# Sim.net
KiCad netlist of a schematic drawn in Altium Designer
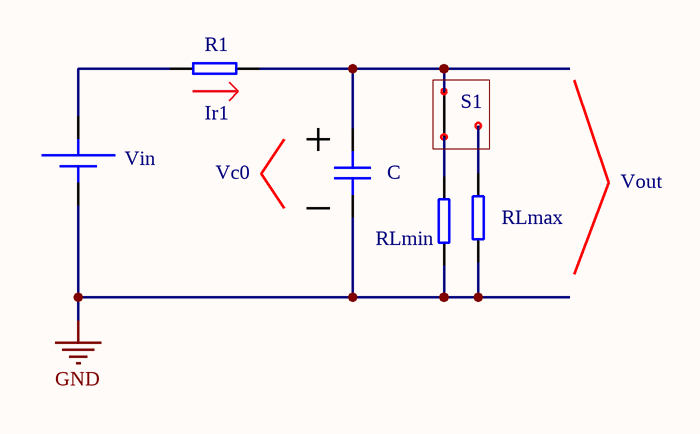
[diagram p0: Sim.SchDoc]

(export (version "E")
  (design (tool "Eeschema 10.0.6"))
  (components
    (comp (ref "C")
      (value "10uF 50V")
      (description "CERAMIC CAPACITOR 10uF 50V 5% -55C TO 125C SMD 0805")
      (libsource (lib "Daagno") (part "CAP 10uF 50V SMD 0805"))
    )
    (comp (ref "R1")
      (value "10K 1/8W")
      (description "CHIP RESISTOR 10K 1/8W 5% -55C TO 125C SMD 0805")
      (libsource (lib "Daagno") (part "RES 10K 1/8W SMD 0805"))
    )
    (comp (ref "RLmax")
      (value "10K 1/8W")
      (description "CHIP RESISTOR 10K 1/8W 5% -55C TO 125C SMD 0805")
      (libsource (lib "Daagno") (part "RES 10K 1/8W SMD 0805"))
    )
    (comp (ref "RLmin")
      (value "10K 1/8W")
      (description "CHIP RESISTOR 10K 1/8W 5% -55C TO 125C SMD 0805")
      (libsource (lib "Daagno") (part "RES 10K 1/8W SMD 0805"))
    )
    (comp (ref "Vin")
      (value "10V")
      (description "GENERIC DC SOURCE FOR SIMULATION")
      (libsource (lib "Daagno") (part "DC SOURCE"))
    )
  )
  (nets
    (net (code "1") (name "GND") (class "Default")
      (node (ref "C") (pin "2") (pinfunction "2_2") (pintype "passive"))
      (node (ref "RLmax") (pin "1") (pinfunction "1_1") (pintype "passive"))
      (node (ref "RLmin") (pin "1") (pinfunction "1_1") (pintype "passive"))
      (node (ref "Vin") (pin "2") (pinfunction "2_2") (pintype "passive"))
    )
    (net (code "2") (name "Net-(C-Pad1)") (class "Default")
      (node (ref "C") (pin "1") (pinfunction "1_1") (pintype "passive"))
      (node (ref "R1") (pin "2") (pinfunction "2_2") (pintype "passive"))
    )
    (net (code "3") (name "Net-(R1-Pad1)") (class "Default")
      (node (ref "R1") (pin "1") (pinfunction "1_1") (pintype "passive"))
      (node (ref "Vin") (pin "1") (pinfunction "1_1") (pintype "passive"))
    )
    (net (code "4") (name "unconnected-(RLmax-Pad2)") (class "Default")
      (node (ref "RLmax") (pin "2") (pinfunction "2_2") (pintype "passive"))
    )
    (net (code "5") (name "unconnected-(RLmin-Pad2)") (class "Default")
      (node (ref "RLmin") (pin "2") (pinfunction "2_2") (pintype "passive"))
    )
  )
)
